# HASP_relay_V_2.net
KiCad netlist of a schematic drawn in EAGLE
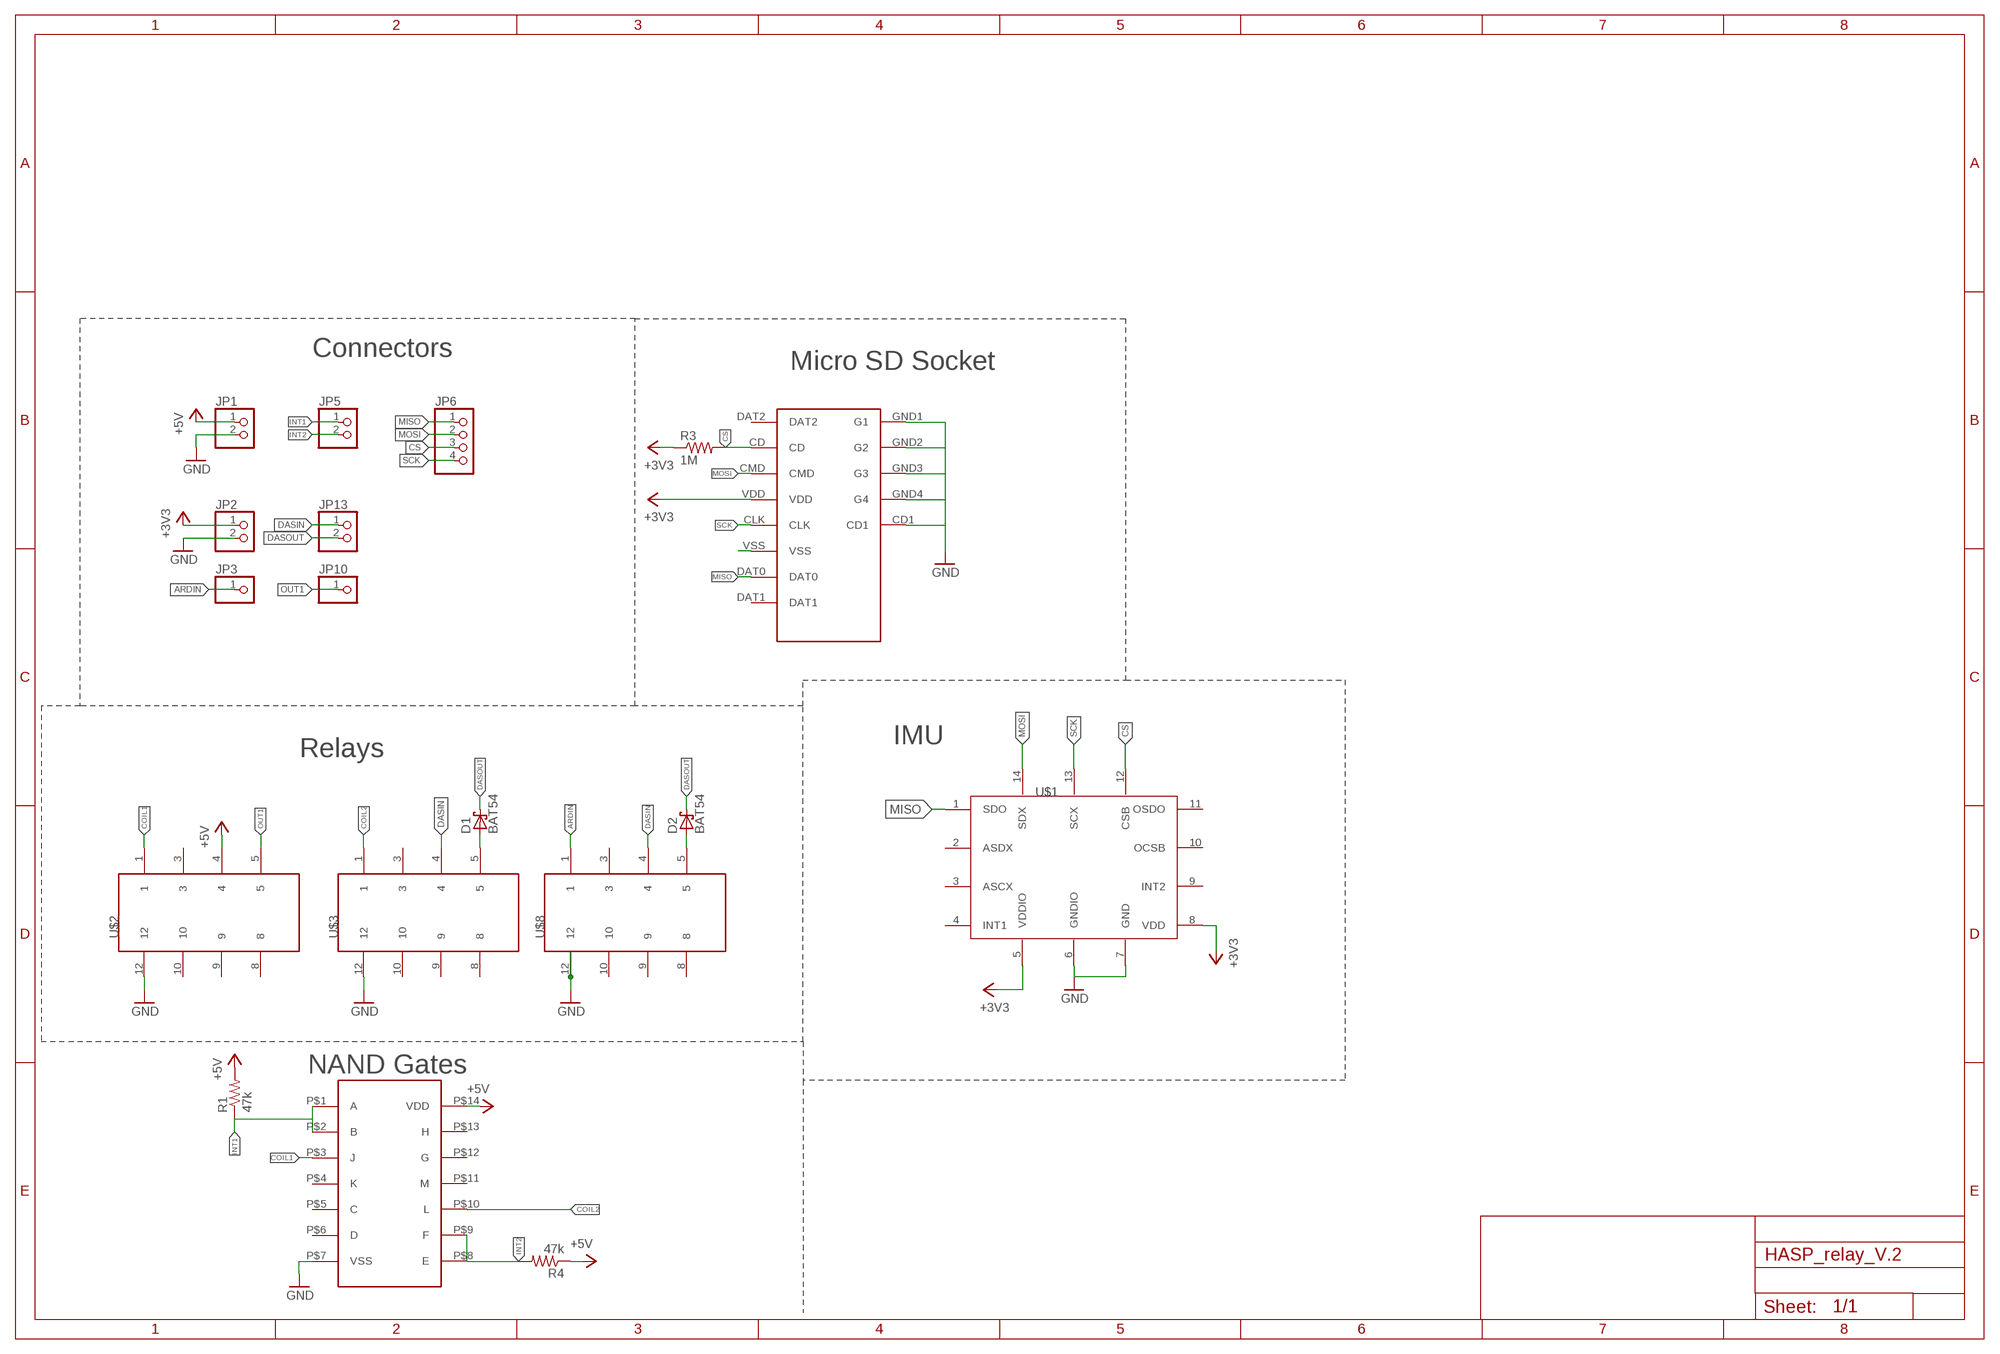
[diagram p0: schematic, sheet 1]

(export (version "E")
  (design (tool "Eeschema 10.0.6"))
  (components
    (comp (ref "D1")
      (value "BAT54")
      (footprint "eagle-import:SOT23")
      (fields (field (name "MF") "ON Semiconductor"))
      (libsource (lib "eagle-import") (part "BAT54"))
    )
    (comp (ref "D2")
      (value "BAT54")
      (footprint "eagle-import:SOT23")
      (fields (field (name "MF") "ON Semiconductor"))
      (libsource (lib "eagle-import") (part "BAT54"))
    )
    (comp (ref "JP1")
      (value "PINHD-1X2")
      (footprint "eagle-import:1X02")
      (libsource (lib "eagle-import") (part "PINHD-1X2"))
    )
    (comp (ref "JP2")
      (value "PINHD-1X2")
      (footprint "eagle-import:1X02")
      (libsource (lib "eagle-import") (part "PINHD-1X2"))
    )
    (comp (ref "JP3")
      (value "PINHD-1X1")
      (footprint "eagle-import:1X01")
      (libsource (lib "eagle-import") (part "PINHD-1X1"))
    )
    (comp (ref "JP5")
      (value "PINHD-1X2")
      (footprint "eagle-import:1X02")
      (libsource (lib "eagle-import") (part "PINHD-1X2"))
    )
    (comp (ref "JP6")
      (value "PINHD-1X4")
      (footprint "eagle-import:1X04")
      (libsource (lib "eagle-import") (part "PINHD-1X4"))
    )
    (comp (ref "JP10")
      (value "PINHD-1X1")
      (footprint "eagle-import:1X01")
      (libsource (lib "eagle-import") (part "PINHD-1X1"))
    )
    (comp (ref "JP13")
      (value "PINHD-1X2")
      (footprint "eagle-import:1X02")
      (libsource (lib "eagle-import") (part "PINHD-1X2"))
    )
    (comp (ref "R1")
      (value "47k")
      (footprint "eagle-import:RESC1608X50N")
      (fields (field (name "MF") "TE Connectivity") (field (name "MP") "CRGS0603J1K5"))
      (libsource (lib "eagle-import") (part "CRGS0603J1K5"))
    )
    (comp (ref "R3")
      (value "1M")
      (footprint "eagle-import:R0603")
      (libsource (lib "eagle-import") (part "R-US_R0603"))
    )
    (comp (ref "R4")
      (value "47k")
      (footprint "eagle-import:RESC1608X50N")
      (fields (field (name "MF") "TE Connectivity") (field (name "MP") "CRGS0603J1K5"))
      (libsource (lib "eagle-import") (part "CRGS0603J1K5"))
    )
    (comp (ref "U$1")
      (value "BMI160")
      (footprint "eagle-import:IMU")
      (libsource (lib "eagle-import") (part "BMI160"))
    )
    (comp (ref "U$2")
      (value "EC2")
      (footprint "eagle-import:EC2-5SNU")
      (libsource (lib "eagle-import") (part "EC2"))
    )
    (comp (ref "U$3")
      (value "EC2")
      (footprint "eagle-import:EC2-5SNU")
      (libsource (lib "eagle-import") (part "EC2"))
    )
    (comp (ref "U$4")
      (value "MICRO_SD")
      (footprint "eagle-import:MICRO_SD_HINGED")
      (libsource (lib "eagle-import") (part "MICRO_SD"))
    )
    (comp (ref "U$5")
      (value "CD4093BE")
      (footprint "eagle-import:CD4093BE")
      (libsource (lib "eagle-import") (part "CD4093BE"))
    )
    (comp (ref "U$8")
      (value "EC2")
      (footprint "eagle-import:EC2-5SNU")
      (libsource (lib "eagle-import") (part "EC2"))
    )
  )
  (nets
    (net (code "1") (name "+3V3") (class "Default")
      (node (ref "JP2") (pin "1") (pinfunction "1_1") (pintype "passive"))
      (node (ref "R3") (pin "1") (pinfunction "1_1") (pintype "passive"))
      (node (ref "U$1") (pin "5") (pinfunction "VDDIO_5") (pintype "power_in"))
      (node (ref "U$1") (pin "8") (pinfunction "VDD_8") (pintype "power_in"))
      (node (ref "U$4") (pin "VDD") (pinfunction "VDD_VDD") (pintype "bidirectional"))
    )
    (net (code "2") (name "+5V") (class "Default")
      (node (ref "JP1") (pin "1") (pinfunction "1_1") (pintype "passive"))
      (node (ref "R1") (pin "2") (pinfunction "2_2") (pintype "passive"))
      (node (ref "R4") (pin "1") (pinfunction "1_1") (pintype "passive"))
      (node (ref "U$2") (pin "4") (pinfunction "4_4") (pintype "bidirectional"))
      (node (ref "U$5") (pin "P$14") (pinfunction "VDD_P$14") (pintype "bidirectional"))
    )
    (net (code "3") (name "ARDIN") (class "Default")
      (node (ref "JP3") (pin "1") (pinfunction "1_1") (pintype "passive"))
      (node (ref "U$8") (pin "1") (pinfunction "1_1") (pintype "bidirectional"))
    )
    (net (code "4") (name "COIL1") (class "Default")
      (node (ref "U$2") (pin "1") (pinfunction "1_1") (pintype "bidirectional"))
      (node (ref "U$5") (pin "P$3") (pinfunction "J_P$3") (pintype "bidirectional"))
    )
    (net (code "5") (name "COIL2") (class "Default")
      (node (ref "U$3") (pin "1") (pinfunction "1_1") (pintype "bidirectional"))
      (node (ref "U$5") (pin "P$10") (pinfunction "L_P$10") (pintype "bidirectional"))
    )
    (net (code "6") (name "CS") (class "Default")
      (node (ref "JP6") (pin "3") (pinfunction "3_3") (pintype "passive"))
      (node (ref "R3") (pin "2") (pinfunction "2_2") (pintype "passive"))
      (node (ref "U$1") (pin "12") (pinfunction "CSB_12") (pintype "input"))
      (node (ref "U$4") (pin "CD") (pinfunction "CD_CD") (pintype "bidirectional"))
    )
    (net (code "7") (name "DASIN") (class "Default")
      (node (ref "JP13") (pin "1") (pinfunction "1_1") (pintype "passive"))
      (node (ref "U$3") (pin "4") (pinfunction "4_4") (pintype "bidirectional"))
      (node (ref "U$8") (pin "4") (pinfunction "4_4") (pintype "bidirectional"))
    )
    (net (code "8") (name "DASOUT") (class "Default")
      (node (ref "D1") (pin "3") (pinfunction "K_3") (pintype "passive"))
      (node (ref "D2") (pin "3") (pinfunction "K_3") (pintype "passive"))
      (node (ref "JP13") (pin "2") (pinfunction "2_2") (pintype "passive"))
    )
    (net (code "9") (name "GND") (class "Default")
      (node (ref "JP1") (pin "2") (pinfunction "2_2") (pintype "passive"))
      (node (ref "JP2") (pin "2") (pinfunction "2_2") (pintype "passive"))
      (node (ref "U$1") (pin "6") (pinfunction "GNDIO_6") (pintype "power_in"))
      (node (ref "U$1") (pin "7") (pinfunction "GND_7") (pintype "power_in"))
      (node (ref "U$2") (pin "12") (pinfunction "12_12") (pintype "bidirectional"))
      (node (ref "U$3") (pin "12") (pinfunction "12_12") (pintype "bidirectional"))
      (node (ref "U$4") (pin "CD1") (pinfunction "CD1_CD1") (pintype "bidirectional"))
      (node (ref "U$4") (pin "GND1") (pinfunction "G1_GND1") (pintype "bidirectional"))
      (node (ref "U$4") (pin "GND2") (pinfunction "G2_GND2") (pintype "bidirectional"))
      (node (ref "U$4") (pin "GND3") (pinfunction "G3_GND3") (pintype "bidirectional"))
      (node (ref "U$4") (pin "GND4") (pinfunction "G4_GND4") (pintype "bidirectional"))
      (node (ref "U$5") (pin "P$7") (pinfunction "VSS_P$7") (pintype "bidirectional"))
      (node (ref "U$8") (pin "12") (pinfunction "12_12") (pintype "bidirectional"))
    )
    (net (code "10") (name "INT1") (class "Default")
      (node (ref "JP5") (pin "1") (pinfunction "1_1") (pintype "passive"))
      (node (ref "U$5") (pin "P$1") (pinfunction "A_P$1") (pintype "bidirectional"))
      (node (ref "U$5") (pin "P$2") (pinfunction "B_P$2") (pintype "bidirectional"))
    )
    (net (code "11") (name "INT2") (class "Default")
      (node (ref "JP5") (pin "2") (pinfunction "2_2") (pintype "passive"))
      (node (ref "R4") (pin "2") (pinfunction "2_2") (pintype "passive"))
      (node (ref "U$5") (pin "P$8") (pinfunction "E_P$8") (pintype "bidirectional"))
      (node (ref "U$5") (pin "P$9") (pinfunction "F_P$9") (pintype "bidirectional"))
    )
    (net (code "12") (name "MISO") (class "Default")
      (node (ref "JP6") (pin "1") (pinfunction "1_1") (pintype "passive"))
      (node (ref "U$1") (pin "1") (pinfunction "SDO_1") (pintype "bidirectional"))
      (node (ref "U$4") (pin "DAT0") (pinfunction "DAT0_DAT0") (pintype "bidirectional"))
    )
    (net (code "13") (name "MOSI") (class "Default")
      (node (ref "JP6") (pin "2") (pinfunction "2_2") (pintype "passive"))
      (node (ref "U$1") (pin "14") (pinfunction "SDX_14") (pintype "bidirectional"))
      (node (ref "U$4") (pin "CMD") (pinfunction "CMD_CMD") (pintype "bidirectional"))
    )
    (net (code "14") (name "Net-(D1-A)") (class "Default")
      (node (ref "D1") (pin "1") (pinfunction "A_1") (pintype "passive"))
      (node (ref "U$3") (pin "5") (pinfunction "5_5") (pintype "bidirectional"))
    )
    (net (code "15") (name "Net-(D2-A)") (class "Default")
      (node (ref "D2") (pin "1") (pinfunction "A_1") (pintype "passive"))
      (node (ref "U$8") (pin "5") (pinfunction "5_5") (pintype "bidirectional"))
    )
    (net (code "16") (name "OUT1") (class "Default")
      (node (ref "JP10") (pin "1") (pinfunction "1_1") (pintype "passive"))
      (node (ref "U$2") (pin "5") (pinfunction "5_5") (pintype "bidirectional"))
    )
    (net (code "17") (name "SCK") (class "Default")
      (node (ref "JP6") (pin "4") (pinfunction "4_4") (pintype "passive"))
      (node (ref "U$1") (pin "13") (pinfunction "SCX_13") (pintype "input"))
      (node (ref "U$4") (pin "CLK") (pinfunction "CLK_CLK") (pintype "bidirectional"))
    )
    (net (code "18") (name "unconnected-(R1-Pad1)") (class "Default")
      (node (ref "R1") (pin "1") (pinfunction "1_1") (pintype "passive"))
    )
    (net (code "19") (name "unconnected-(U$1-ASCX-Pad3)") (class "Default")
      (node (ref "U$1") (pin "3") (pinfunction "ASCX_3") (pintype "output"))
    )
    (net (code "20") (name "unconnected-(U$1-ASDX-Pad2)") (class "Default")
      (node (ref "U$1") (pin "2") (pinfunction "ASDX_2") (pintype "bidirectional"))
    )
    (net (code "21") (name "unconnected-(U$1-INT1-Pad4)") (class "Default")
      (node (ref "U$1") (pin "4") (pinfunction "INT1_4") (pintype "bidirectional"))
    )
    (net (code "22") (name "unconnected-(U$1-INT2-Pad9)") (class "Default")
      (node (ref "U$1") (pin "9") (pinfunction "INT2_9") (pintype "bidirectional"))
    )
    (net (code "23") (name "unconnected-(U$1-OCSB-Pad10)") (class "Default")
      (node (ref "U$1") (pin "10") (pinfunction "OCSB_10") (pintype "bidirectional"))
    )
    (net (code "24") (name "unconnected-(U$1-OSDO-Pad11)") (class "Default")
      (node (ref "U$1") (pin "11") (pinfunction "OSDO_11") (pintype "bidirectional"))
    )
    (net (code "25") (name "unconnected-(U$2-Pad3)") (class "Default")
      (node (ref "U$2") (pin "3") (pinfunction "3_3") (pintype "bidirectional"))
    )
    (net (code "26") (name "unconnected-(U$2-Pad8)") (class "Default")
      (node (ref "U$2") (pin "8") (pinfunction "8_8") (pintype "bidirectional"))
    )
    (net (code "27") (name "unconnected-(U$2-Pad9)") (class "Default")
      (node (ref "U$2") (pin "9") (pinfunction "9_9") (pintype "bidirectional"))
    )
    (net (code "28") (name "unconnected-(U$2-Pad10)") (class "Default")
      (node (ref "U$2") (pin "10") (pinfunction "10_10") (pintype "bidirectional"))
    )
    (net (code "29") (name "unconnected-(U$3-Pad3)") (class "Default")
      (node (ref "U$3") (pin "3") (pinfunction "3_3") (pintype "bidirectional"))
    )
    (net (code "30") (name "unconnected-(U$3-Pad8)") (class "Default")
      (node (ref "U$3") (pin "8") (pinfunction "8_8") (pintype "bidirectional"))
    )
    (net (code "31") (name "unconnected-(U$3-Pad9)") (class "Default")
      (node (ref "U$3") (pin "9") (pinfunction "9_9") (pintype "bidirectional"))
    )
    (net (code "32") (name "unconnected-(U$3-Pad10)") (class "Default")
      (node (ref "U$3") (pin "10") (pinfunction "10_10") (pintype "bidirectional"))
    )
    (net (code "33") (name "unconnected-(U$4-PadDAT1)") (class "Default")
      (node (ref "U$4") (pin "DAT1") (pinfunction "DAT1_DAT1") (pintype "bidirectional"))
    )
    (net (code "34") (name "unconnected-(U$4-PadDAT2)") (class "Default")
      (node (ref "U$4") (pin "DAT2") (pinfunction "DAT2_DAT2") (pintype "bidirectional"))
    )
    (net (code "35") (name "unconnected-(U$4-PadVSS)") (class "Default")
      (node (ref "U$4") (pin "VSS") (pinfunction "VSS_VSS") (pintype "bidirectional"))
    )
    (net (code "36") (name "unconnected-(U$5-C-PadP$5)") (class "Default")
      (node (ref "U$5") (pin "P$5") (pinfunction "C_P$5") (pintype "bidirectional"))
    )
    (net (code "37") (name "unconnected-(U$5-D-PadP$6)") (class "Default")
      (node (ref "U$5") (pin "P$6") (pinfunction "D_P$6") (pintype "bidirectional"))
    )
    (net (code "38") (name "unconnected-(U$5-G-PadP$12)") (class "Default")
      (node (ref "U$5") (pin "P$12") (pinfunction "G_P$12") (pintype "bidirectional"))
    )
    (net (code "39") (name "unconnected-(U$5-H-PadP$13)") (class "Default")
      (node (ref "U$5") (pin "P$13") (pinfunction "H_P$13") (pintype "bidirectional"))
    )
    (net (code "40") (name "unconnected-(U$5-K-PadP$4)") (class "Default")
      (node (ref "U$5") (pin "P$4") (pinfunction "K_P$4") (pintype "bidirectional"))
    )
    (net (code "41") (name "unconnected-(U$5-M-PadP$11)") (class "Default")
      (node (ref "U$5") (pin "P$11") (pinfunction "M_P$11") (pintype "bidirectional"))
    )
    (net (code "42") (name "unconnected-(U$8-Pad3)") (class "Default")
      (node (ref "U$8") (pin "3") (pinfunction "3_3") (pintype "bidirectional"))
    )
    (net (code "43") (name "unconnected-(U$8-Pad8)") (class "Default")
      (node (ref "U$8") (pin "8") (pinfunction "8_8") (pintype "bidirectional"))
    )
    (net (code "44") (name "unconnected-(U$8-Pad9)") (class "Default")
      (node (ref "U$8") (pin "9") (pinfunction "9_9") (pintype "bidirectional"))
    )
    (net (code "45") (name "unconnected-(U$8-Pad10)") (class "Default")
      (node (ref "U$8") (pin "10") (pinfunction "10_10") (pintype "bidirectional"))
    )
  )
)
